# Simple_Converter.net
KiCad netlist of a schematic drawn in Altium Designer
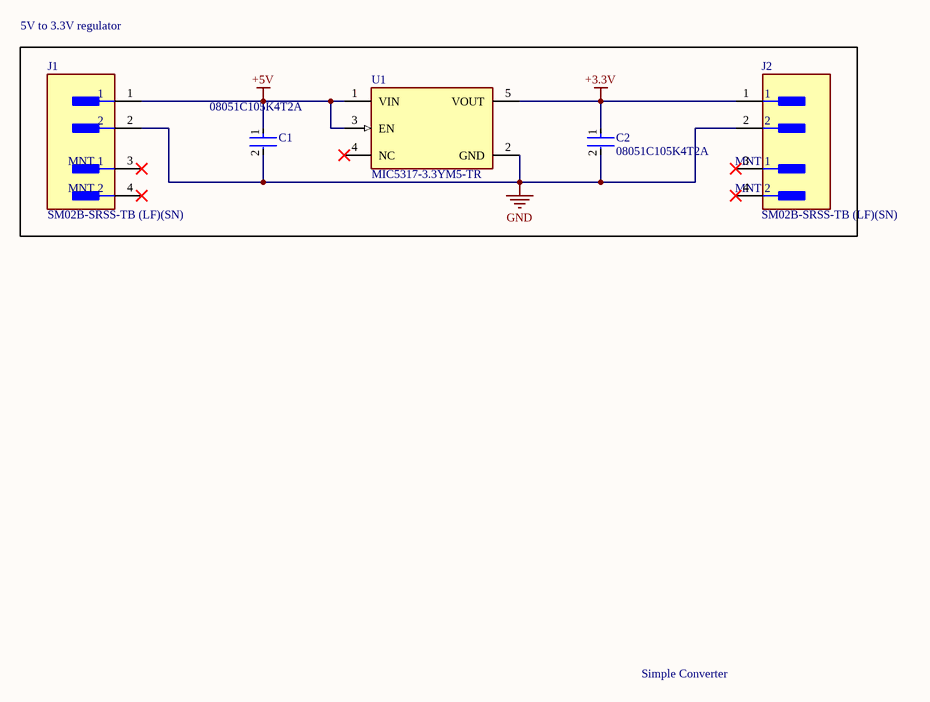
[diagram p0: Simple Converter.SchDoc]

(export (version "E")
  (design (tool "Eeschema 10.0.6"))
  (components
    (comp (ref "C1")
      (value "08051C105K4T2A")
      (footprint "FP-0805-L_2_01_0_2-W_1_25-MFG")
      (description "08051C105K4T2A Cap Ceramic 1uF 100V X7R 10% Pad SMD 0805 125C Automotive T/R")
      (fields (field (name "TOLERANCE") "10%"))
      (libsource (lib "Altium Content Vault") (part "b4654b650e69147ec39a6b967a45e02"))
    )
    (comp (ref "C2")
      (value "08051C105K4T2A")
      (footprint "FP-0805-L_2_01_0_2-W_1_25-MFG")
      (description "08051C105K4T2A Cap Ceramic 1uF 100V X7R 10% Pad SMD 0805 125C Automotive T/R")
      (fields (field (name "TOLERANCE") "10%"))
      (libsource (lib "Altium Content Vault") (part "b4654b650e69147ec39a6b967a45e02"))
    )
    (comp (ref "J1")
      (value "SM02B-SRSS-TB (LF)(SN)")
      (footprint "FP-SM02B-SRSS-TB_LF_SN-MFG")
      (description "CONN HEADER SMD R/A 2POS 1MM")
      (libsource (lib "Altium Content Vault") (part "029478cb6d4f2fad0cd2a245525ee6d"))
    )
    (comp (ref "J2")
      (value "SM02B-SRSS-TB (LF)(SN)")
      (footprint "FP-SM02B-SRSS-TB_LF_SN-MFG")
      (description "CONN HEADER SMD R/A 2POS 1MM")
      (libsource (lib "") (part "029478cb6d4f2fad0cd2a245525ee6d_1"))
    )
    (comp (ref "U1")
      (value "MIC5317-3.3YM5-TR")
      (footprint "FP-SOT23-5LD-PL-1-MFG")
      (description "IC REG LINEAR 3.3V 150MA SOT23-5")
      (libsource (lib "Altium Content Vault") (part "0a093dae7315cdc977fd108dde87457"))
    )
  )
  (nets
    (net (code "1") (name "+3.3V") (class "Default")
      (node (ref "C2") (pin "1") (pinfunction "1_1") (pintype "passive"))
      (node (ref "J2") (pin "1") (pinfunction "1_1") (pintype "passive"))
      (node (ref "U1") (pin "5") (pinfunction "VOUT_5") (pintype "power_in"))
    )
    (net (code "2") (name "+5V") (class "Default")
      (node (ref "C1") (pin "1") (pinfunction "1_1") (pintype "passive"))
      (node (ref "J1") (pin "1") (pinfunction "1_1") (pintype "passive"))
      (node (ref "U1") (pin "1") (pinfunction "VIN_1") (pintype "power_in"))
      (node (ref "U1") (pin "3") (pinfunction "EN_3") (pintype "input"))
    )
    (net (code "3") (name "GND") (class "Default")
      (node (ref "C1") (pin "2") (pinfunction "2_2") (pintype "passive"))
      (node (ref "C2") (pin "2") (pinfunction "2_2") (pintype "passive"))
      (node (ref "J1") (pin "2") (pinfunction "2_2") (pintype "passive"))
      (node (ref "J2") (pin "2") (pinfunction "2_2") (pintype "passive"))
      (node (ref "U1") (pin "2") (pinfunction "GND_2") (pintype "power_in"))
    )
    (net (code "4") (name "unconnected-(J1-MNT_1-Pad3)") (class "Default")
      (node (ref "J1") (pin "3") (pinfunction "MNT_1_3") (pintype "passive+no_connect"))
    )
    (net (code "5") (name "unconnected-(J1-MNT_2-Pad4)") (class "Default")
      (node (ref "J1") (pin "4") (pinfunction "MNT_2_4") (pintype "passive+no_connect"))
    )
    (net (code "6") (name "unconnected-(J2-MNT_1-Pad3)") (class "Default")
      (node (ref "J2") (pin "3") (pinfunction "MNT_1_3") (pintype "passive+no_connect"))
    )
    (net (code "7") (name "unconnected-(J2-MNT_2-Pad4)") (class "Default")
      (node (ref "J2") (pin "4") (pinfunction "MNT_2_4") (pintype "passive+no_connect"))
    )
    (net (code "8") (name "unconnected-(U1-NC-Pad4)") (class "Default")
      (node (ref "U1") (pin "4") (pinfunction "NC_4") (pintype "passive+no_connect"))
    )
  )
)
